# Hall_sensor.net
KiCad netlist of a schematic drawn in Altium Designer
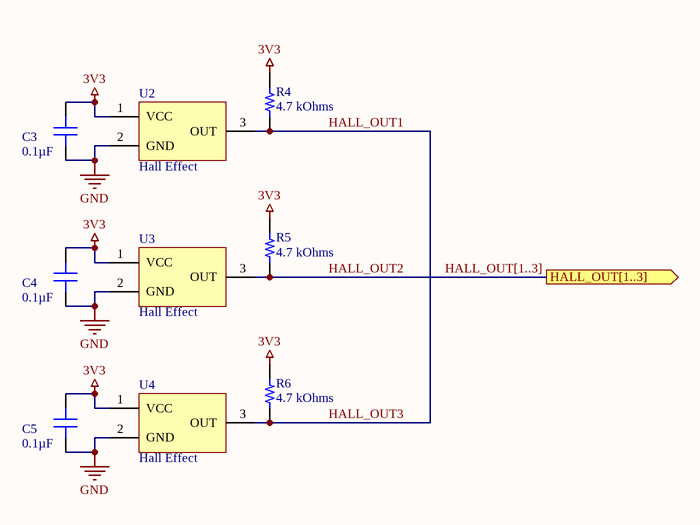
[diagram p0: Hall_sensor.SchDoc]

(export (version "E")
  (design (tool "Eeschema 10.0.6"))
  (components
    (comp (ref "C3")
      (value "0.1µF")
      (footprint "CAP 0603_1608")
      (description "CAP CER 0.1UF 100V 0603 EPOXY")
      (fields
        (field (name "PART NUMBER") "GCG188R92A104KA03D")
        (field (name "MANUFACTURER") "Murata Electronics")
      )
      (libsource (lib "Celestial Altium Library - altium_library") (part "Capacitor"))
    )
    (comp (ref "C4")
      (value "0.1µF")
      (footprint "CAP 0603_1608")
      (description "CAP CER 0.1UF 100V 0603 EPOXY")
      (fields
        (field (name "PART NUMBER") "GCG188R92A104KA03D")
        (field (name "MANUFACTURER") "Murata Electronics")
      )
      (libsource (lib "Celestial Altium Library - altium_library") (part "Capacitor"))
    )
    (comp (ref "C5")
      (value "0.1µF")
      (footprint "CAP 0603_1608")
      (description "CAP CER 0.1UF 100V 0603 EPOXY")
      (fields
        (field (name "PART NUMBER") "GCG188R92A104KA03D")
        (field (name "MANUFACTURER") "Murata Electronics")
      )
      (libsource (lib "Celestial Altium Library - altium_library") (part "Capacitor"))
    )
    (comp (ref "R4")
      (value "4.7 kOhms")
      (footprint "RES 0603_1608")
      (description "RES SMD 4.7K OHM 1% 1/10W 0603")
      (fields (field (name "PART NUMBER") "CRCW06034K70FKTA") (field (name "MANUFACTURER") "Vishay Dale"))
      (libsource (lib "Celestial Altium Library - altium_library") (part "Resistor"))
    )
    (comp (ref "R5")
      (value "4.7 kOhms")
      (footprint "RES 0603_1608")
      (description "RES SMD 4.7K OHM 1% 1/10W 0603")
      (fields (field (name "PART NUMBER") "CRCW06034K70FKTA") (field (name "MANUFACTURER") "Vishay Dale"))
      (libsource (lib "Celestial Altium Library - altium_library") (part "Resistor"))
    )
    (comp (ref "R6")
      (value "4.7 kOhms")
      (footprint "RES 0603_1608")
      (description "RES SMD 4.7K OHM 1% 1/10W 0603")
      (fields (field (name "PART NUMBER") "CRCW06034K70FKTA") (field (name "MANUFACTURER") "Vishay Dale"))
      (libsource (lib "Celestial Altium Library - altium_library") (part "Resistor"))
    )
    (comp (ref "U2") (value "Hall Effect") (footprint "DRV5011ADLPG") (libsource (lib "IC") (part "DRV5011")))
    (comp (ref "U3") (value "Hall Effect") (footprint "DRV5011ADLPG") (libsource (lib "IC") (part "DRV5011")))
    (comp (ref "U4") (value "Hall Effect") (footprint "DRV5011ADLPG") (libsource (lib "IC") (part "DRV5011")))
  )
  (nets
    (net (code "1") (name "/HALL_OUT1") (class "Default")
      (node (ref "R4") (pin "1") (pinfunction "1_1") (pintype "passive"))
      (node (ref "U2") (pin "3") (pinfunction "OUT_3") (pintype "passive"))
    )
    (net (code "2") (name "/HALL_OUT2") (class "Default")
      (node (ref "R5") (pin "2") (pinfunction "2_2") (pintype "passive"))
      (node (ref "U3") (pin "3") (pinfunction "OUT_3") (pintype "passive"))
    )
    (net (code "3") (name "/HALL_OUT3") (class "Default")
      (node (ref "R6") (pin "2") (pinfunction "2_2") (pintype "passive"))
      (node (ref "U4") (pin "3") (pinfunction "OUT_3") (pintype "passive"))
    )
    (net (code "5") (name "3V3") (class "Default")
      (node (ref "C3") (pin "1") (pinfunction "1_1") (pintype "passive"))
      (node (ref "C4") (pin "1") (pinfunction "1_1") (pintype "passive"))
      (node (ref "C5") (pin "1") (pinfunction "1_1") (pintype "passive"))
      (node (ref "R4") (pin "2") (pinfunction "2_2") (pintype "passive"))
      (node (ref "R5") (pin "1") (pinfunction "1_1") (pintype "passive"))
      (node (ref "R6") (pin "1") (pinfunction "1_1") (pintype "passive"))
      (node (ref "U2") (pin "1") (pinfunction "VCC_1") (pintype "passive"))
      (node (ref "U3") (pin "1") (pinfunction "VCC_1") (pintype "passive"))
      (node (ref "U4") (pin "1") (pinfunction "VCC_1") (pintype "passive"))
    )
    (net (code "6") (name "GND") (class "Default")
      (node (ref "C3") (pin "2") (pinfunction "2_2") (pintype "passive"))
      (node (ref "C4") (pin "2") (pinfunction "2_2") (pintype "passive"))
      (node (ref "C5") (pin "2") (pinfunction "2_2") (pintype "passive"))
      (node (ref "U2") (pin "2") (pinfunction "GND_2") (pintype "passive"))
      (node (ref "U3") (pin "2") (pinfunction "GND_2") (pintype "passive"))
      (node (ref "U4") (pin "2") (pinfunction "GND_2") (pintype "passive"))
    )
  )
)
